# ADCS.net
KiCad netlist of a schematic drawn in Altium Designer
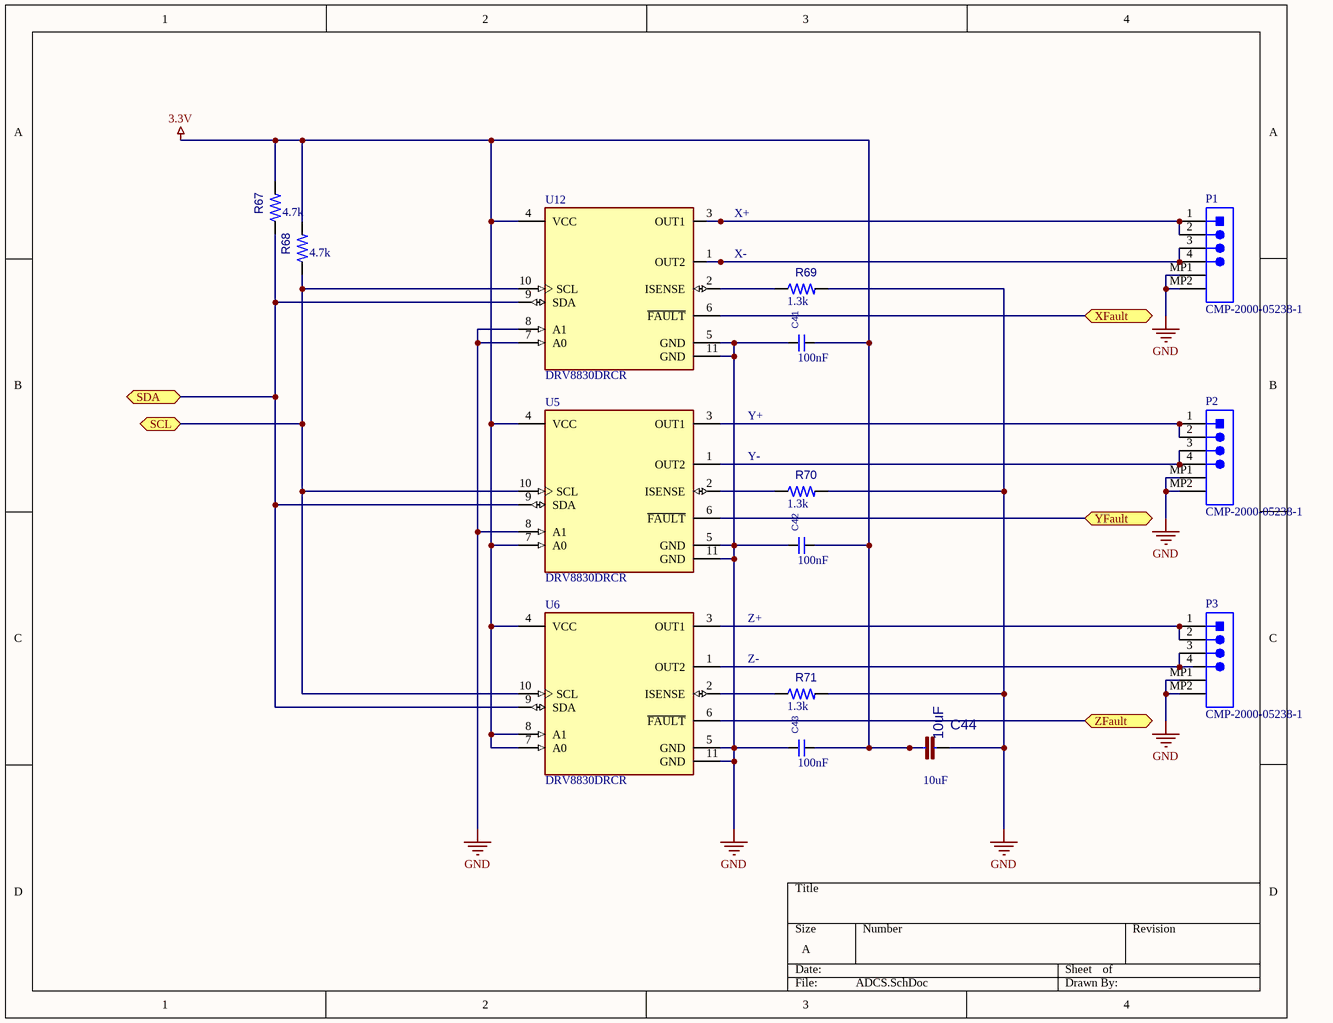
[diagram p0: ADCS.SchDoc]

(export (version "E")
  (design (tool "Eeschema 10.0.6"))
  (components
    (comp (ref "C41")
      (value "100nF")
      (footprint "Resistor_0805")
      (fields (field (name "MPN") "CL21B104KBCNNNC"))
      (libsource (lib "mainboard_1") (part "CL21B104KBCNNNC"))
    )
    (comp (ref "C42")
      (value "100nF")
      (footprint "Resistor_0805")
      (fields (field (name "MPN") "CL21B104KBCNNNC"))
      (libsource (lib "mainboard_1") (part "CL21B104KBCNNNC"))
    )
    (comp (ref "C43")
      (value "100nF")
      (footprint "Resistor_0805")
      (fields (field (name "MPN") "CL21B104KBCNNNC"))
      (libsource (lib "mainboard_1") (part "CL21B104KBCNNNC"))
    )
    (comp (ref "C44")
      (value "10uF")
      (footprint "C_0603_1608Metric")
      (fields (field (name "MPN") "1210ZC106KAT2A") (field (name "ALTIUM_VALUE") "10uF"))
      (libsource (lib "mainboard_1") (part "1210ZC106KAT2A"))
    )
    (comp (ref "P1")
      (value "CMP-2000-05238-1")
      (footprint "MOLEX-53261-0471_V")
      (description "Male Header, Pitch 1.25 mm, 1 x 4 Position, Height 3.4 mm, -40 to 85 degC, RoHS, Tape and Reel")
      (fields (field (name "MPN") "0533984004"))
      (libsource (lib "mainboard_1") (part "CMP-2000-05238-1"))
    )
    (comp (ref "P2")
      (value "CMP-2000-05238-1")
      (footprint "MOLEX-53261-0471_V")
      (description "Male Header, Pitch 1.25 mm, 1 x 4 Position, Height 3.4 mm, -40 to 85 degC, RoHS, Tape and Reel")
      (fields (field (name "MPN") "0533984004"))
      (libsource (lib "mainboard_1") (part "CMP-2000-05238-1"))
    )
    (comp (ref "P3")
      (value "CMP-2000-05238-1")
      (footprint "MOLEX-53261-0471_V")
      (description "Male Header, Pitch 1.25 mm, 1 x 4 Position, Height 3.4 mm, -40 to 85 degC, RoHS, Tape and Reel")
      (fields (field (name "MPN") "0533984004"))
      (libsource (lib "mainboard_1") (part "CMP-2000-05238-1"))
    )
    (comp (ref "R67")
      (value "4.7k")
      (footprint "L_0805_2012Metric_Pad1.15x1.40mm_HandSolder")
      (fields (field (name "MPN") "RC0805FR-074K7L"))
      (libsource (lib "mainboard_1") (part "RC0805FR-074K7L"))
    )
    (comp (ref "R68")
      (value "4.7k")
      (footprint "L_0805_2012Metric_Pad1.15x1.40mm_HandSolder")
      (fields (field (name "MPN") "RC0805FR-074K7L"))
      (libsource (lib "mainboard_1") (part "RC0805FR-074K7L"))
    )
    (comp (ref "R69")
      (value "1.3k")
      (footprint "L_0805_2012Metric_Pad1.15x1.40mm_HandSolder")
      (fields (field (name "MPN") "ERJ-6ENF1301V"))
      (libsource (lib "mainboard_1") (part "ERJ-6ENF1301V"))
    )
    (comp (ref "R70")
      (value "1.3k")
      (footprint "L_0805_2012Metric_Pad1.15x1.40mm_HandSolder")
      (fields (field (name "MPN") "ERJ-6ENF1301V"))
      (libsource (lib "mainboard_1") (part "ERJ-6ENF1301V"))
    )
    (comp (ref "R71")
      (value "1.3k")
      (footprint "L_0805_2012Metric_Pad1.15x1.40mm_HandSolder")
      (fields (field (name "MPN") "ERJ-6ENF1301V"))
      (libsource (lib "mainboard_1") (part "ERJ-6ENF1301V"))
    )
    (comp (ref "U5")
      (value "DRV8830DRCR")
      (footprint "FP-DRC0010J-MFG")
      (description "IC MTRDRV BIPLR 2.75-6.8V 10VSON")
      (fields
        (field (name "OCTOPART") "https://octopart.com/drv8830drcr-texas+instruments-21221812")
        (field (name "MANUFACTURER") "Texas Instruments")
      )
      (libsource (lib "mainboard_1") (part "CMP-04915-000001-1"))
    )
    (comp (ref "U6")
      (value "DRV8830DRCR")
      (footprint "FP-DRC0010J-MFG")
      (description "IC MTRDRV BIPLR 2.75-6.8V 10VSON")
      (fields
        (field (name "OCTOPART") "https://octopart.com/drv8830drcr-texas+instruments-21221812")
        (field (name "MANUFACTURER") "Texas Instruments")
      )
      (libsource (lib "mainboard_1") (part "CMP-04915-000001-1"))
    )
    (comp (ref "U12")
      (value "DRV8830DRCR")
      (footprint "FP-DRC0010J-MFG")
      (description "IC MTRDRV BIPLR 2.75-6.8V 10VSON")
      (fields
        (field (name "OCTOPART") "https://octopart.com/drv8830drcr-texas+instruments-21221812")
        (field (name "MANUFACTURER") "Texas Instruments")
      )
      (libsource (lib "mainboard_1") (part "CMP-04915-000001-1"))
    )
  )
  (nets
    (net (code "1") (name "/SCL") (class "Default")
      (node (ref "R68") (pin "1") (pinfunction "1_1") (pintype "passive"))
      (node (ref "U12") (pin "10") (pinfunction "SCL_10") (pintype "input"))
      (node (ref "U5") (pin "10") (pinfunction "SCL_10") (pintype "input"))
      (node (ref "U6") (pin "10") (pinfunction "SCL_10") (pintype "input"))
    )
    (net (code "2") (name "/SDA") (class "Default")
      (node (ref "R67") (pin "1") (pinfunction "1_1") (pintype "passive"))
      (node (ref "U12") (pin "9") (pinfunction "SDA_9") (pintype "bidirectional"))
      (node (ref "U5") (pin "9") (pinfunction "SDA_9") (pintype "bidirectional"))
      (node (ref "U6") (pin "9") (pinfunction "SDA_9") (pintype "bidirectional"))
    )
    (net (code "3") (name "/XFault") (class "Default")
      (node (ref "U12") (pin "6") (pinfunction "~{FAULT}_6") (pintype "open_collector"))
    )
    (net (code "4") (name "/YFault") (class "Default")
      (node (ref "U5") (pin "6") (pinfunction "~{FAULT}_6") (pintype "open_collector"))
    )
    (net (code "5") (name "/ZFault") (class "Default")
      (node (ref "U6") (pin "6") (pinfunction "~{FAULT}_6") (pintype "open_collector"))
    )
    (net (code "6") (name "3.3V") (class "Default")
      (node (ref "C41") (pin "2") (pinfunction "2_2") (pintype "passive"))
      (node (ref "C42") (pin "2") (pinfunction "2_2") (pintype "passive"))
      (node (ref "C43") (pin "2") (pinfunction "2_2") (pintype "passive"))
      (node (ref "C44") (pin "1") (pinfunction "1_1") (pintype "passive"))
      (node (ref "R67") (pin "2") (pinfunction "2_2") (pintype "passive"))
      (node (ref "R68") (pin "2") (pinfunction "2_2") (pintype "passive"))
      (node (ref "U12") (pin "4") (pinfunction "VCC_4") (pintype "power_in"))
      (node (ref "U5") (pin "4") (pinfunction "VCC_4") (pintype "power_in"))
      (node (ref "U5") (pin "7") (pinfunction "A0_7") (pintype "input"))
      (node (ref "U6") (pin "4") (pinfunction "VCC_4") (pintype "power_in"))
      (node (ref "U6") (pin "7") (pinfunction "A0_7") (pintype "input"))
      (node (ref "U6") (pin "8") (pinfunction "A1_8") (pintype "input"))
    )
    (net (code "7") (name "GND") (class "Default")
      (node (ref "C41") (pin "1") (pinfunction "1_1") (pintype "passive"))
      (node (ref "C42") (pin "1") (pinfunction "1_1") (pintype "passive"))
      (node (ref "C43") (pin "1") (pinfunction "1_1") (pintype "passive"))
      (node (ref "C44") (pin "2") (pinfunction "2_2") (pintype "passive"))
      (node (ref "P1") (pin "MP1") (pinfunction "MP1_MP1") (pintype "passive"))
      (node (ref "P1") (pin "MP2") (pinfunction "MP2_MP2") (pintype "passive"))
      (node (ref "P2") (pin "MP1") (pinfunction "MP1_MP1") (pintype "passive"))
      (node (ref "P2") (pin "MP2") (pinfunction "MP2_MP2") (pintype "passive"))
      (node (ref "P3") (pin "MP1") (pinfunction "MP1_MP1") (pintype "passive"))
      (node (ref "P3") (pin "MP2") (pinfunction "MP2_MP2") (pintype "passive"))
      (node (ref "R69") (pin "2") (pinfunction "2_2") (pintype "passive"))
      (node (ref "R70") (pin "2") (pinfunction "2_2") (pintype "passive"))
      (node (ref "R71") (pin "2") (pinfunction "2_2") (pintype "passive"))
      (node (ref "U12") (pin "11") (pinfunction "GND_11") (pintype "power_in"))
      (node (ref "U12") (pin "5") (pinfunction "GND_5") (pintype "power_in"))
      (node (ref "U12") (pin "7") (pinfunction "A0_7") (pintype "input"))
      (node (ref "U12") (pin "8") (pinfunction "A1_8") (pintype "input"))
      (node (ref "U5") (pin "11") (pinfunction "GND_11") (pintype "power_in"))
      (node (ref "U5") (pin "5") (pinfunction "GND_5") (pintype "power_in"))
      (node (ref "U5") (pin "8") (pinfunction "A1_8") (pintype "input"))
      (node (ref "U6") (pin "11") (pinfunction "GND_11") (pintype "power_in"))
      (node (ref "U6") (pin "5") (pinfunction "GND_5") (pintype "power_in"))
    )
    (net (code "8") (name "Net-(U5-ISENSE)") (class "Default")
      (node (ref "R70") (pin "1") (pinfunction "1_1") (pintype "passive"))
      (node (ref "U5") (pin "2") (pinfunction "ISENSE_2") (pintype "bidirectional"))
    )
    (net (code "9") (name "Net-(U5-OUT1)") (class "Default")
      (node (ref "P2") (pin "1") (pinfunction "1_1") (pintype "passive"))
      (node (ref "P2") (pin "2") (pinfunction "2_2") (pintype "passive"))
      (node (ref "U5") (pin "3") (pinfunction "OUT1_3") (pintype "power_in"))
    )
    (net (code "10") (name "Net-(U5-OUT2)") (class "Default")
      (node (ref "P2") (pin "3") (pinfunction "3_3") (pintype "passive"))
      (node (ref "P2") (pin "4") (pinfunction "4_4") (pintype "passive"))
      (node (ref "U5") (pin "1") (pinfunction "OUT2_1") (pintype "power_in"))
    )
    (net (code "11") (name "Net-(U6-ISENSE)") (class "Default")
      (node (ref "R71") (pin "1") (pinfunction "1_1") (pintype "passive"))
      (node (ref "U6") (pin "2") (pinfunction "ISENSE_2") (pintype "bidirectional"))
    )
    (net (code "12") (name "Net-(U6-OUT1)") (class "Default")
      (node (ref "P3") (pin "1") (pinfunction "1_1") (pintype "passive"))
      (node (ref "P3") (pin "2") (pinfunction "2_2") (pintype "passive"))
      (node (ref "U6") (pin "3") (pinfunction "OUT1_3") (pintype "power_in"))
    )
    (net (code "13") (name "Net-(U6-OUT2)") (class "Default")
      (node (ref "P3") (pin "3") (pinfunction "3_3") (pintype "passive"))
      (node (ref "P3") (pin "4") (pinfunction "4_4") (pintype "passive"))
      (node (ref "U6") (pin "1") (pinfunction "OUT2_1") (pintype "power_in"))
    )
    (net (code "14") (name "Net-(U12-ISENSE)") (class "Default")
      (node (ref "R69") (pin "1") (pinfunction "1_1") (pintype "passive"))
      (node (ref "U12") (pin "2") (pinfunction "ISENSE_2") (pintype "bidirectional"))
    )
    (net (code "15") (name "Net-(U12-OUT1)") (class "Default")
      (node (ref "P1") (pin "1") (pinfunction "1_1") (pintype "passive"))
      (node (ref "P1") (pin "2") (pinfunction "2_2") (pintype "passive"))
      (node (ref "U12") (pin "3") (pinfunction "OUT1_3") (pintype "power_in"))
    )
    (net (code "16") (name "Net-(U12-OUT2)") (class "Default")
      (node (ref "P1") (pin "3") (pinfunction "3_3") (pintype "passive"))
      (node (ref "P1") (pin "4") (pinfunction "4_4") (pintype "passive"))
      (node (ref "U12") (pin "1") (pinfunction "OUT2_1") (pintype "power_in"))
    )
  )
)
